# FED3_v6_3.net
KiCad netlist of a schematic drawn in EAGLE
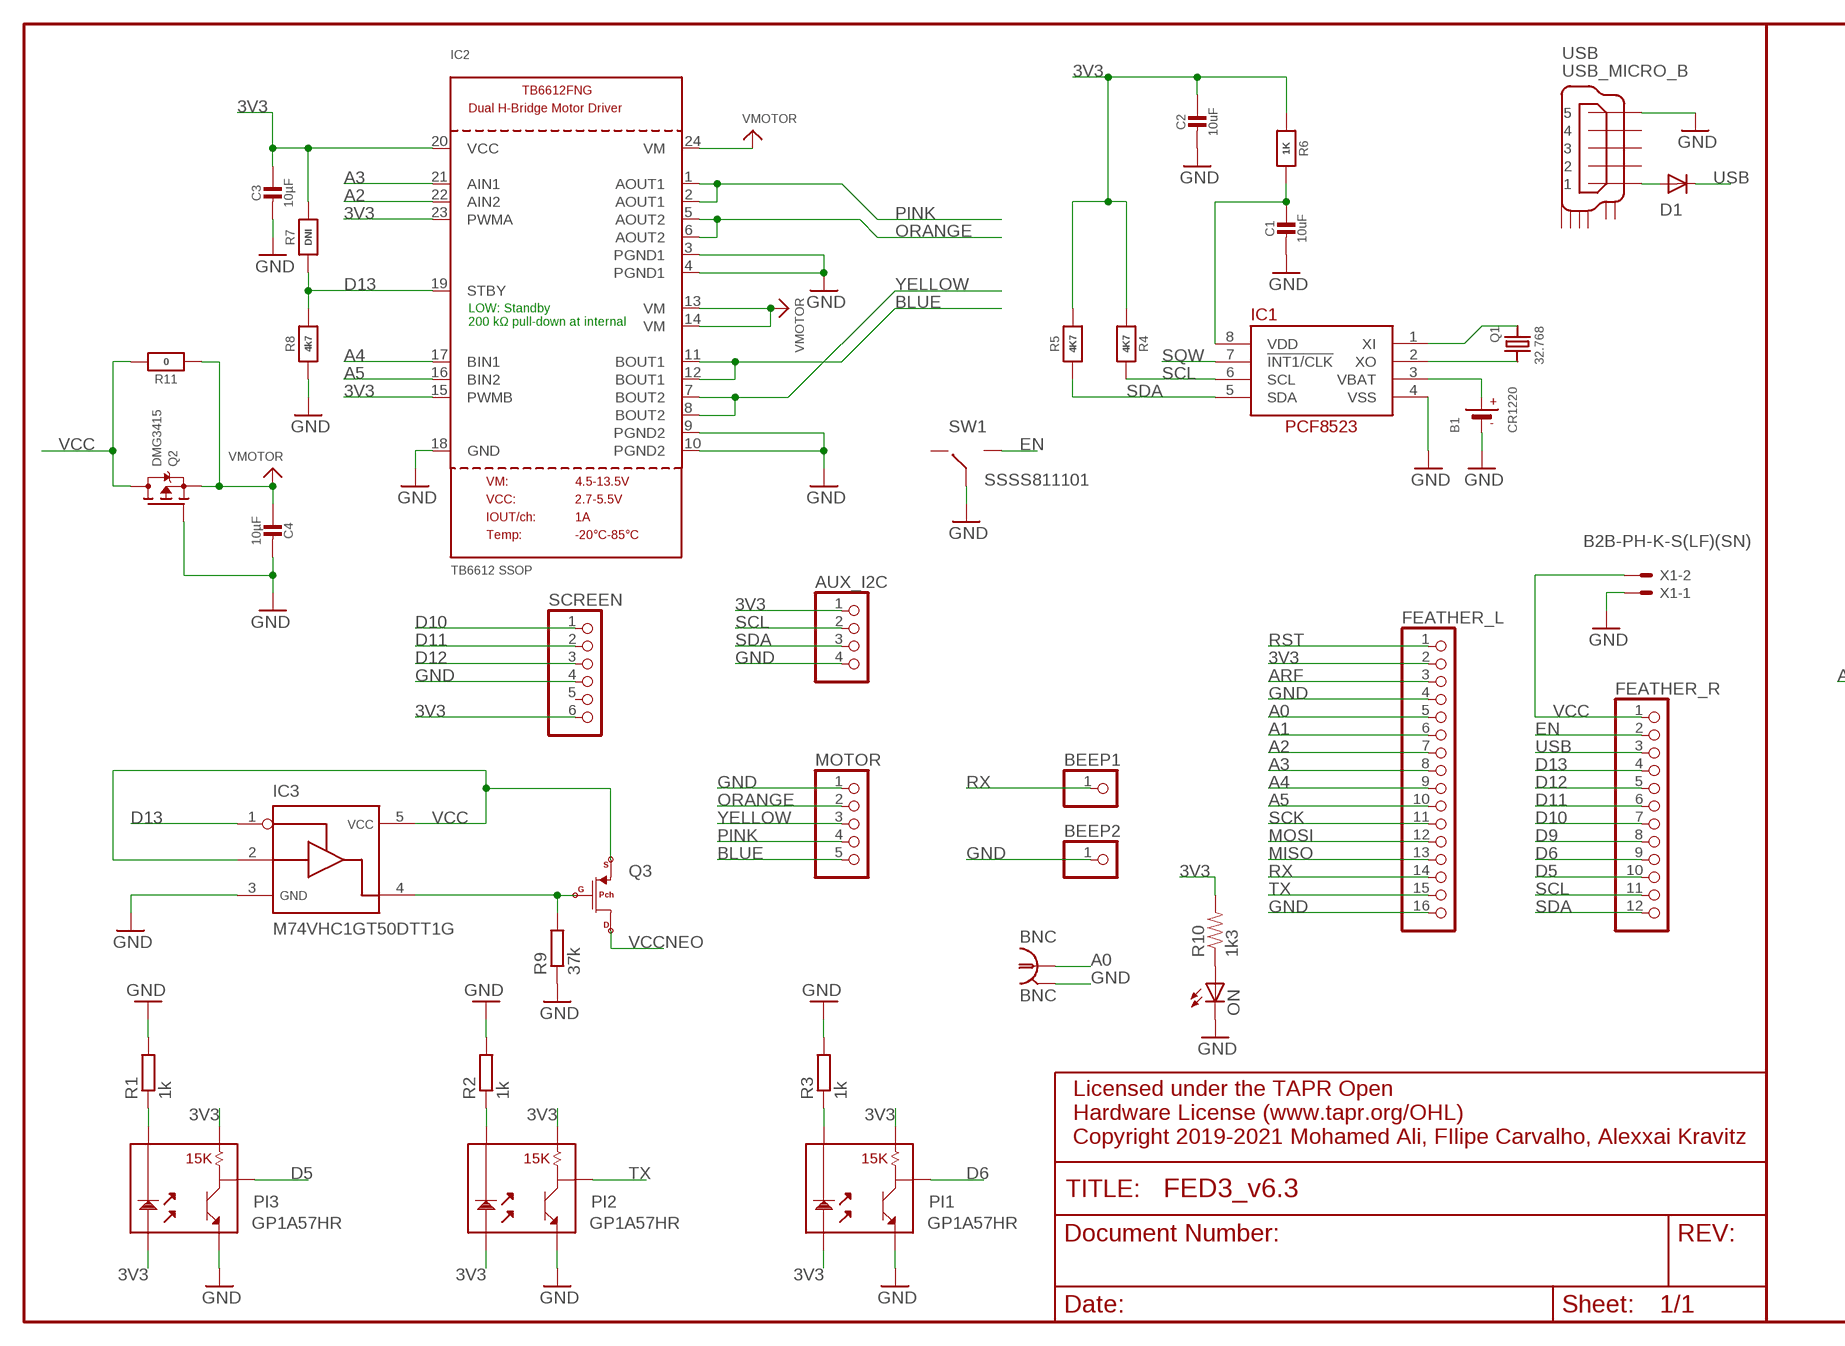
[diagram p0: schematic, sheet 1, part 1 of 2]
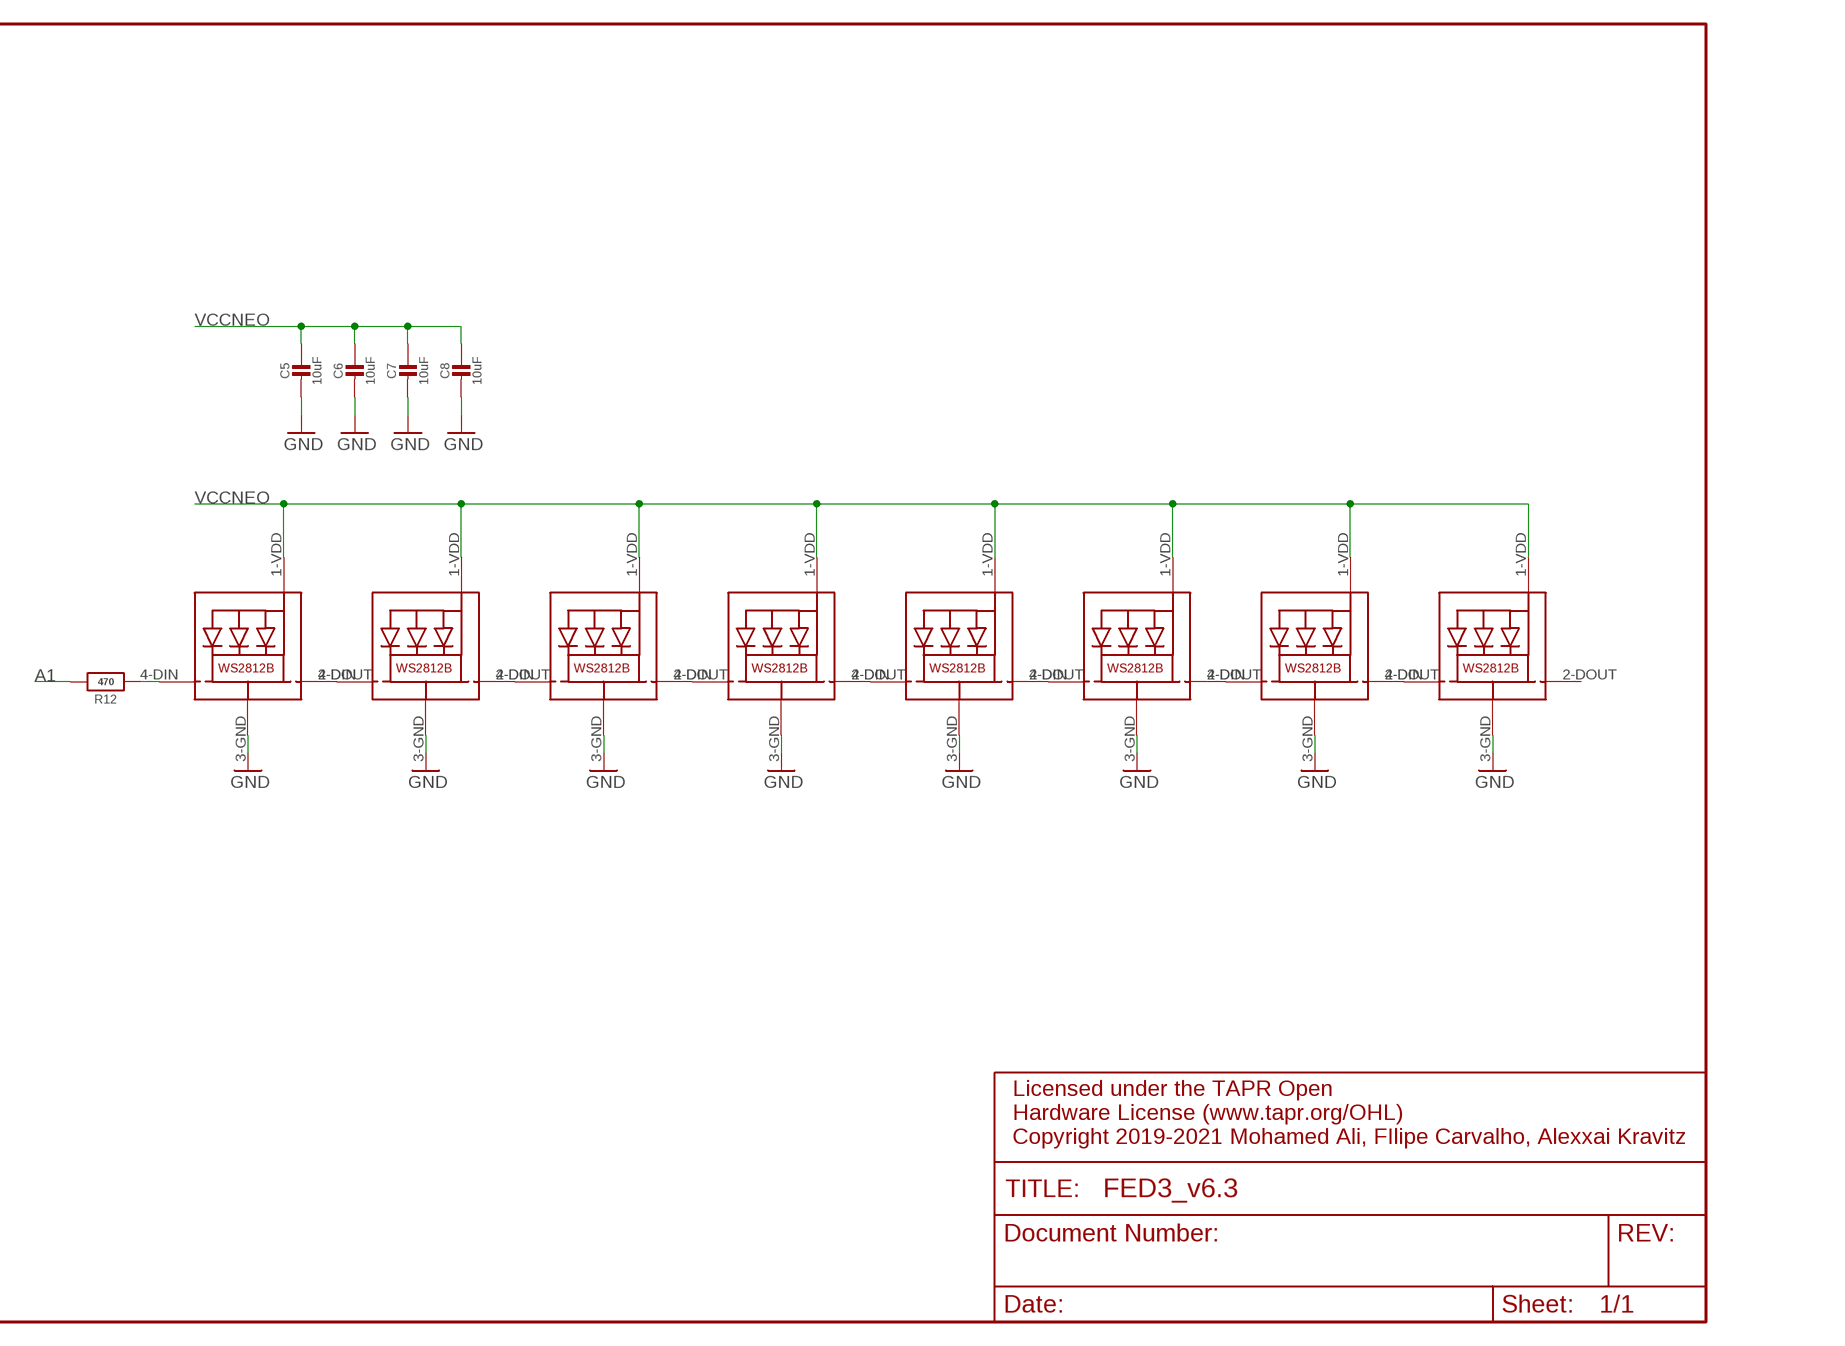
[diagram p1: schematic, sheet 1, part 2 of 2]

(export (version "E")
  (design (tool "Eeschema 10.0.6"))
  (components
    (comp (ref "AUX_I2C")
      (value "PINHD-1X4")
      (footprint "eagle-import:1X04")
      (libsource (lib "eagle-import") (part "PINHD-1X4"))
    )
    (comp (ref "B1")
      (value "CR1220")
      (footprint "eagle-import:CR1220")
      (libsource (lib "eagle-import") (part "BATTERYCR1220_SMT"))
    )
    (comp (ref "BEEP1")
      (value "PINHD-1X1")
      (footprint "eagle-import:1X01")
      (libsource (lib "eagle-import") (part "PINHD-1X1"))
    )
    (comp (ref "BEEP2")
      (value "PINHD-1X1")
      (footprint "eagle-import:1X01")
      (libsource (lib "eagle-import") (part "PINHD-1X1"))
    )
    (comp (ref "BNC")
      (value "BNC")
      (footprint "eagle-import:BNC_RA")
      (libsource (lib "eagle-import") (part "BNC"))
    )
    (comp (ref "C1")
      (value "10uF")
      (footprint "eagle-import:0805-NO")
      (libsource (lib "eagle-import") (part "CAP_CERAMIC0805-NOOUTLINE"))
    )
    (comp (ref "C2")
      (value "10uF")
      (footprint "eagle-import:0805-NO")
      (libsource (lib "eagle-import") (part "CAP_CERAMIC0805-NOOUTLINE"))
    )
    (comp (ref "C3")
      (value "10µF")
      (footprint "eagle-import:0805-NO")
      (libsource (lib "eagle-import") (part "CAP_CERAMIC0805-NOOUTLINE"))
    )
    (comp (ref "C4")
      (value "10µF")
      (footprint "eagle-import:0805-NO")
      (libsource (lib "eagle-import") (part "CAP_CERAMIC0805-NOOUTLINE"))
    )
    (comp (ref "C5")
      (value "10uF")
      (footprint "eagle-import:0805-NO")
      (libsource (lib "eagle-import") (part "CAP_CERAMIC0805-NOOUTLINE"))
    )
    (comp (ref "C6")
      (value "10uF")
      (footprint "eagle-import:0805-NO")
      (libsource (lib "eagle-import") (part "CAP_CERAMIC0805-NOOUTLINE"))
    )
    (comp (ref "C7")
      (value "10uF")
      (footprint "eagle-import:0805-NO")
      (libsource (lib "eagle-import") (part "CAP_CERAMIC0805-NOOUTLINE"))
    )
    (comp (ref "C8")
      (value "10uF")
      (footprint "eagle-import:0805-NO")
      (libsource (lib "eagle-import") (part "CAP_CERAMIC0805-NOOUTLINE"))
    )
    (comp (ref "D1")
      (value "DIODE-DO-214AC")
      (footprint "eagle-import:DO-214AC")
      (libsource (lib "eagle-import") (part "DIODE-DO-214AC"))
    )
    (comp (ref "FEATHER_L")
      (value "PINHD-1X16")
      (footprint "eagle-import:1X16")
      (libsource (lib "eagle-import") (part "PINHD-1X16"))
    )
    (comp (ref "FEATHER_R")
      (value "PINHD-1X12")
      (footprint "eagle-import:1X12")
      (libsource (lib "eagle-import") (part "PINHD-1X12"))
    )
    (comp (ref "IC1")
      (value "RTC_PCF8523T")
      (footprint "eagle-import:SOIC8_150MIL")
      (libsource (lib "eagle-import") (part "RTC_PCF8523T"))
    )
    (comp (ref "IC2")
      (value "TB6612 SSOP")
      (footprint "eagle-import:SSOP24")
      (libsource (lib "eagle-import") (part "TB6612FNGSSOP"))
    )
    (comp (ref "IC3")
      (value "M74VHC1GT50DTT1G")
      (footprint "eagle-import:SOT23-5")
      (libsource (lib "eagle-import") (part "SN74LVC1G125"))
    )
    (comp (ref "LED1")
      (value "WS2812B5050")
      (footprint "eagle-import:WS2812B")
      (libsource (lib "eagle-import") (part "WS2812B5050"))
    )
    (comp (ref "LED2")
      (value "WS2812B5050")
      (footprint "eagle-import:WS2812B")
      (libsource (lib "eagle-import") (part "WS2812B5050"))
    )
    (comp (ref "LED3")
      (value "WS2812B5050")
      (footprint "eagle-import:WS2812B")
      (libsource (lib "eagle-import") (part "WS2812B5050"))
    )
    (comp (ref "LED4")
      (value "WS2812B5050")
      (footprint "eagle-import:WS2812B")
      (libsource (lib "eagle-import") (part "WS2812B5050"))
    )
    (comp (ref "LED5")
      (value "WS2812B5050")
      (footprint "eagle-import:WS2812B")
      (libsource (lib "eagle-import") (part "WS2812B5050"))
    )
    (comp (ref "LED6")
      (value "WS2812B5050")
      (footprint "eagle-import:WS2812B")
      (libsource (lib "eagle-import") (part "WS2812B5050"))
    )
    (comp (ref "LED7")
      (value "WS2812B5050")
      (footprint "eagle-import:WS2812B")
      (libsource (lib "eagle-import") (part "WS2812B5050"))
    )
    (comp (ref "LED8")
      (value "WS2812B5050")
      (footprint "eagle-import:WS2812B")
      (libsource (lib "eagle-import") (part "WS2812B5050"))
    )
    (comp (ref "MOTOR")
      (value "PINHD-1X5")
      (footprint "eagle-import:1X05")
      (libsource (lib "eagle-import") (part "PINHD-1X5"))
    )
    (comp (ref "ON")
      (value "LEDCHIPLED_0603")
      (footprint "eagle-import:CHIPLED_0603")
      (libsource (lib "eagle-import") (part "LEDCHIPLED_0603"))
    )
    (comp (ref "PI1")
      (value "GP1A57HR")
      (footprint "eagle-import:GP1A57HR")
      (libsource (lib "eagle-import") (part "GP1A57HR"))
    )
    (comp (ref "PI2")
      (value "GP1A57HR")
      (footprint "eagle-import:GP1A57HR")
      (libsource (lib "eagle-import") (part "GP1A57HR"))
    )
    (comp (ref "PI3")
      (value "GP1A57HR")
      (footprint "eagle-import:GP1A57HR")
      (libsource (lib "eagle-import") (part "GP1A57HR"))
    )
    (comp (ref "Q1")
      (value "32.768")
      (footprint "eagle-import:CRYSTAL_8X3.8")
      (libsource (lib "eagle-import") (part "CRYSTAL8.0X3.8"))
    )
    (comp (ref "Q2")
      (value "DMG3415")
      (footprint "eagle-import:SOT23-WIDE")
      (libsource (lib "eagle-import") (part "MOSFET-PWIDE"))
    )
    (comp (ref "Q3")
      (value "MOSFET_P-CH")
      (footprint "eagle-import:TSMT3")
      (libsource (lib "eagle-import") (part "MOSFET_P-CH"))
    )
    (comp (ref "R1")
      (value "1k")
      (footprint "eagle-import:R0805")
      (libsource (lib "eagle-import") (part "R-EU_R0805"))
    )
    (comp (ref "R2")
      (value "1k")
      (footprint "eagle-import:R0805")
      (libsource (lib "eagle-import") (part "R-EU_R0805"))
    )
    (comp (ref "R3")
      (value "1k")
      (footprint "eagle-import:R0805")
      (libsource (lib "eagle-import") (part "R-EU_R0805"))
    )
    (comp (ref "R4")
      (value "4K7")
      (footprint "eagle-import:0805-NO")
      (libsource (lib "eagle-import") (part "RESISTOR0805_NOOUTLINE"))
    )
    (comp (ref "R5")
      (value "4K7")
      (footprint "eagle-import:0805-NO")
      (libsource (lib "eagle-import") (part "RESISTOR0805_NOOUTLINE"))
    )
    (comp (ref "R6")
      (value "1K")
      (footprint "eagle-import:0805-NO")
      (libsource (lib "eagle-import") (part "RESISTOR0805_NOOUTLINE"))
    )
    (comp (ref "R7")
      (value "DNI")
      (footprint "eagle-import:0805-NO")
      (libsource (lib "eagle-import") (part "RESISTOR0805_NOOUTLINE"))
    )
    (comp (ref "R8")
      (value "4k7")
      (footprint "eagle-import:0805-NO")
      (libsource (lib "eagle-import") (part "RESISTOR0805_NOOUTLINE"))
    )
    (comp (ref "R9")
      (value "37k")
      (footprint "eagle-import:R0805")
      (libsource (lib "eagle-import") (part "R-EU_R0805"))
    )
    (comp (ref "R10")
      (value "1k3")
      (footprint "eagle-import:0805")
      (libsource (lib "eagle-import") (part "RESISTOR"))
    )
    (comp (ref "R11")
      (value "0")
      (footprint "eagle-import:0805-NO")
      (libsource (lib "eagle-import") (part "RESISTOR0805_NOOUTLINE"))
    )
    (comp (ref "R12")
      (value "470")
      (footprint "eagle-import:0805-NO")
      (libsource (lib "eagle-import") (part "RESISTOR0805_NOOUTLINE"))
    )
    (comp (ref "SCREEN")
      (value "PINHD-1X6")
      (footprint "eagle-import:1X06")
      (libsource (lib "eagle-import") (part "PINHD-1X6"))
    )
    (comp (ref "SW1")
      (value "SSSS811101")
      (footprint "eagle-import:SSSS811101")
      (libsource (lib "eagle-import") (part "SSSS811101"))
    )
    (comp (ref "USB")
      (value "USB_MICRO_B")
      (footprint "eagle-import:ZX62D-B-5P8")
      (libsource (lib "eagle-import") (part "USB_MICRO_B"))
    )
    (comp (ref "X1")
      (value "B2B-PH-K-S(LF)(SN)")
      (footprint "eagle-import:JST-XH-02-PACKAGE-ROUND-PAD")
      (libsource (lib "eagle-import") (part "JST-XH-02-PIN-ROUND-PAD"))
    )
  )
  (nets
    (net (code "1") (name "/3V3") (class "Default")
      (node (ref "AUX_I2C") (pin "1") (pinfunction "1_1") (pintype "passive"))
      (node (ref "C2") (pin "1") (pinfunction "1_1") (pintype "passive"))
      (node (ref "C3") (pin "1") (pinfunction "1_1") (pintype "passive"))
      (node (ref "FEATHER_L") (pin "2") (pinfunction "2_2") (pintype "passive"))
      (node (ref "IC2") (pin "15") (pinfunction "PWMB_15") (pintype "input"))
      (node (ref "IC2") (pin "20") (pinfunction "VCC_20") (pintype "power_in"))
      (node (ref "IC2") (pin "23") (pinfunction "PWMA_23") (pintype "input"))
      (node (ref "PI1") (pin "1") (pinfunction "1_1") (pintype "bidirectional"))
      (node (ref "PI1") (pin "3") (pinfunction "3_3") (pintype "bidirectional"))
      (node (ref "PI2") (pin "1") (pinfunction "1_1") (pintype "bidirectional"))
      (node (ref "PI2") (pin "3") (pinfunction "3_3") (pintype "bidirectional"))
      (node (ref "PI3") (pin "1") (pinfunction "1_1") (pintype "bidirectional"))
      (node (ref "PI3") (pin "3") (pinfunction "3_3") (pintype "bidirectional"))
      (node (ref "R10") (pin "2") (pinfunction "2_2") (pintype "passive"))
      (node (ref "R4") (pin "1") (pinfunction "1_1") (pintype "passive"))
      (node (ref "R5") (pin "2") (pinfunction "2_2") (pintype "passive"))
      (node (ref "R6") (pin "1") (pinfunction "1_1") (pintype "passive"))
      (node (ref "R7") (pin "2") (pinfunction "2_2") (pintype "passive"))
      (node (ref "SCREEN") (pin "6") (pinfunction "6_6") (pintype "passive"))
    )
    (net (code "2") (name "/A0") (class "Default")
      (node (ref "BNC") (pin "1") (pinfunction "1_1") (pintype "passive"))
      (node (ref "FEATHER_L") (pin "5") (pinfunction "5_5") (pintype "passive"))
    )
    (net (code "3") (name "/A1") (class "Default")
      (node (ref "FEATHER_L") (pin "6") (pinfunction "6_6") (pintype "passive"))
      (node (ref "R12") (pin "2") (pinfunction "2_2") (pintype "passive"))
    )
    (net (code "4") (name "/A2") (class "Default")
      (node (ref "FEATHER_L") (pin "7") (pinfunction "7_7") (pintype "passive"))
      (node (ref "IC2") (pin "22") (pinfunction "AIN2_22") (pintype "input"))
    )
    (net (code "5") (name "/A3") (class "Default")
      (node (ref "FEATHER_L") (pin "8") (pinfunction "8_8") (pintype "passive"))
      (node (ref "IC2") (pin "21") (pinfunction "AIN1_21") (pintype "input"))
    )
    (net (code "6") (name "/A4") (class "Default")
      (node (ref "FEATHER_L") (pin "9") (pinfunction "9_9") (pintype "passive"))
      (node (ref "IC2") (pin "17") (pinfunction "BIN1_17") (pintype "input"))
    )
    (net (code "7") (name "/A5") (class "Default")
      (node (ref "FEATHER_L") (pin "10") (pinfunction "10_10") (pintype "passive"))
      (node (ref "IC2") (pin "16") (pinfunction "BIN2_16") (pintype "input"))
    )
    (net (code "8") (name "/ARF") (class "Default")
      (node (ref "FEATHER_L") (pin "3") (pinfunction "3_3") (pintype "passive"))
    )
    (net (code "9") (name "/BLUE") (class "Default")
      (node (ref "IC2") (pin "11") (pinfunction "BOUT1_11") (pintype "output"))
      (node (ref "IC2") (pin "12") (pinfunction "BOUT1_12") (pintype "output"))
      (node (ref "MOTOR") (pin "5") (pinfunction "5_5") (pintype "passive"))
    )
    (net (code "10") (name "/D5") (class "Default")
      (node (ref "FEATHER_R") (pin "10") (pinfunction "10_10") (pintype "passive"))
      (node (ref "PI3") (pin "4") (pinfunction "4_4") (pintype "bidirectional"))
    )
    (net (code "11") (name "/D6") (class "Default")
      (node (ref "FEATHER_R") (pin "9") (pinfunction "9_9") (pintype "passive"))
      (node (ref "PI1") (pin "4") (pinfunction "4_4") (pintype "bidirectional"))
    )
    (net (code "12") (name "/D9") (class "Default")
      (node (ref "FEATHER_R") (pin "8") (pinfunction "8_8") (pintype "passive"))
    )
    (net (code "13") (name "/D10") (class "Default")
      (node (ref "FEATHER_R") (pin "7") (pinfunction "7_7") (pintype "passive"))
      (node (ref "SCREEN") (pin "1") (pinfunction "1_1") (pintype "passive"))
    )
    (net (code "14") (name "/D11") (class "Default")
      (node (ref "FEATHER_R") (pin "6") (pinfunction "6_6") (pintype "passive"))
      (node (ref "SCREEN") (pin "2") (pinfunction "2_2") (pintype "passive"))
    )
    (net (code "15") (name "/D12") (class "Default")
      (node (ref "FEATHER_R") (pin "5") (pinfunction "5_5") (pintype "passive"))
      (node (ref "SCREEN") (pin "3") (pinfunction "3_3") (pintype "passive"))
    )
    (net (code "16") (name "/D13") (class "Default")
      (node (ref "FEATHER_R") (pin "4") (pinfunction "4_4") (pintype "passive"))
      (node (ref "IC2") (pin "19") (pinfunction "STBY_19") (pintype "input"))
      (node (ref "IC3") (pin "1") (pinfunction "P$1_1") (pintype "bidirectional"))
      (node (ref "R7") (pin "1") (pinfunction "1_1") (pintype "passive"))
      (node (ref "R8") (pin "2") (pinfunction "2_2") (pintype "passive"))
    )
    (net (code "17") (name "/EN") (class "Default")
      (node (ref "FEATHER_R") (pin "2") (pinfunction "2_2") (pintype "passive"))
      (node (ref "SW1") (pin "3") (pinfunction "3_3") (pintype "bidirectional"))
    )
    (net (code "18") (name "/MISO") (class "Default")
      (node (ref "FEATHER_L") (pin "13") (pinfunction "13_13") (pintype "passive"))
    )
    (net (code "19") (name "/MOSI") (class "Default")
      (node (ref "FEATHER_L") (pin "12") (pinfunction "12_12") (pintype "passive"))
    )
    (net (code "20") (name "/ORANGE") (class "Default")
      (node (ref "IC2") (pin "5") (pinfunction "AOUT2_5") (pintype "output"))
      (node (ref "IC2") (pin "6") (pinfunction "AOUT2_6") (pintype "output"))
      (node (ref "MOTOR") (pin "2") (pinfunction "2_2") (pintype "passive"))
    )
    (net (code "21") (name "/PINK") (class "Default")
      (node (ref "IC2") (pin "1") (pinfunction "AOUT1_1") (pintype "output"))
      (node (ref "IC2") (pin "2") (pinfunction "AOUT1_2") (pintype "output"))
      (node (ref "MOTOR") (pin "4") (pinfunction "4_4") (pintype "passive"))
    )
    (net (code "22") (name "/RST") (class "Default")
      (node (ref "FEATHER_L") (pin "1") (pinfunction "1_1") (pintype "passive"))
    )
    (net (code "23") (name "/RX") (class "Default")
      (node (ref "BEEP1") (pin "1") (pinfunction "1_1") (pintype "passive"))
      (node (ref "FEATHER_L") (pin "14") (pinfunction "14_14") (pintype "passive"))
    )
    (net (code "24") (name "/SCK") (class "Default")
      (node (ref "FEATHER_L") (pin "11") (pinfunction "11_11") (pintype "passive"))
    )
    (net (code "25") (name "/SCL") (class "Default")
      (node (ref "AUX_I2C") (pin "2") (pinfunction "2_2") (pintype "passive"))
      (node (ref "FEATHER_R") (pin "11") (pinfunction "11_11") (pintype "passive"))
      (node (ref "IC1") (pin "6") (pinfunction "SCL_6") (pintype "bidirectional"))
      (node (ref "R4") (pin "2") (pinfunction "2_2") (pintype "passive"))
    )
    (net (code "26") (name "/SDA") (class "Default")
      (node (ref "AUX_I2C") (pin "3") (pinfunction "3_3") (pintype "passive"))
      (node (ref "FEATHER_R") (pin "12") (pinfunction "12_12") (pintype "passive"))
      (node (ref "IC1") (pin "5") (pinfunction "SDA_5") (pintype "bidirectional"))
      (node (ref "R5") (pin "1") (pinfunction "1_1") (pintype "passive"))
    )
    (net (code "27") (name "/SQW") (class "Default")
      (node (ref "IC1") (pin "7") (pinfunction "~{INT1/CLK}_7") (pintype "output"))
    )
    (net (code "28") (name "/TX") (class "Default")
      (node (ref "FEATHER_L") (pin "15") (pinfunction "15_15") (pintype "passive"))
      (node (ref "PI2") (pin "4") (pinfunction "4_4") (pintype "bidirectional"))
    )
    (net (code "29") (name "/USB") (class "Default")
      (node (ref "D1") (pin "C") (pinfunction "C_C") (pintype "passive"))
      (node (ref "FEATHER_R") (pin "3") (pinfunction "3_3") (pintype "passive"))
    )
    (net (code "30") (name "/VCC") (class "Default")
      (node (ref "FEATHER_R") (pin "1") (pinfunction "1_1") (pintype "passive"))
      (node (ref "IC3") (pin "2") (pinfunction "P$2_2") (pintype "bidirectional"))
      (node (ref "IC3") (pin "5") (pinfunction "P$5_5") (pintype "bidirectional"))
      (node (ref "Q2") (pin "3") (pinfunction "D_3") (pintype "passive"))
      (node (ref "Q3") (pin "P$2") (pinfunction "S_P$2") (pintype "passive"))
      (node (ref "R11") (pin "2") (pinfunction "2_2") (pintype "passive"))
      (node (ref "X1") (pin "2") (pinfunction "S_2") (pintype "passive"))
    )
    (net (code "31") (name "/VCCNEO") (class "Default")
      (node (ref "C5") (pin "1") (pinfunction "1_1") (pintype "passive"))
      (node (ref "C6") (pin "1") (pinfunction "1_1") (pintype "passive"))
      (node (ref "C7") (pin "1") (pinfunction "1_1") (pintype "passive"))
      (node (ref "C8") (pin "1") (pinfunction "1_1") (pintype "passive"))
      (node (ref "LED1") (pin "1-VDD") (pinfunction "VDD_1-VDD") (pintype "power_in"))
      (node (ref "LED2") (pin "1-VDD") (pinfunction "VDD_1-VDD") (pintype "power_in"))
      (node (ref "LED3") (pin "1-VDD") (pinfunction "VDD_1-VDD") (pintype "power_in"))
      (node (ref "LED4") (pin "1-VDD") (pinfunction "VDD_1-VDD") (pintype "power_in"))
      (node (ref "LED5") (pin "1-VDD") (pinfunction "VDD_1-VDD") (pintype "power_in"))
      (node (ref "LED6") (pin "1-VDD") (pinfunction "VDD_1-VDD") (pintype "power_in"))
      (node (ref "LED7") (pin "1-VDD") (pinfunction "VDD_1-VDD") (pintype "power_in"))
      (node (ref "LED8") (pin "1-VDD") (pinfunction "VDD_1-VDD") (pintype "power_in"))
      (node (ref "Q3") (pin "P$3") (pinfunction "D_P$3") (pintype "passive"))
    )
    (net (code "32") (name "/YELLOW") (class "Default")
      (node (ref "IC2") (pin "7") (pinfunction "BOUT2_7") (pintype "output"))
      (node (ref "IC2") (pin "8") (pinfunction "BOUT2_8") (pintype "output"))
      (node (ref "MOTOR") (pin "3") (pinfunction "3_3") (pintype "passive"))
    )
    (net (code "33") (name "GND") (class "Default")
      (node (ref "AUX_I2C") (pin "4") (pinfunction "4_4") (pintype "passive"))
      (node (ref "B1") (pin "-") (pinfunction "-_-") (pintype "passive"))
      (node (ref "BEEP2") (pin "1") (pinfunction "1_1") (pintype "passive"))
      (node (ref "BNC") (pin "2") (pinfunction "2_2") (pintype "passive"))
      (node (ref "C1") (pin "2") (pinfunction "2_2") (pintype "passive"))
      (node (ref "C2") (pin "2") (pinfunction "2_2") (pintype "passive"))
      (node (ref "C3") (pin "2") (pinfunction "2_2") (pintype "passive"))
      (node (ref "C4") (pin "2") (pinfunction "2_2") (pintype "passive"))
      (node (ref "C5") (pin "2") (pinfunction "2_2") (pintype "passive"))
      (node (ref "C6") (pin "2") (pinfunction "2_2") (pintype "passive"))
      (node (ref "C7") (pin "2") (pinfunction "2_2") (pintype "passive"))
      (node (ref "C8") (pin "2") (pinfunction "2_2") (pintype "passive"))
      (node (ref "FEATHER_L") (pin "16") (pinfunction "16_16") (pintype "passive"))
      (node (ref "FEATHER_L") (pin "4") (pinfunction "4_4") (pintype "passive"))
      (node (ref "IC1") (pin "4") (pinfunction "VSS_4") (pintype "power_in"))
      (node (ref "IC2") (pin "10") (pinfunction "PGND2_10") (pintype "power_in"))
      (node (ref "IC2") (pin "18") (pinfunction "GND_18") (pintype "power_in"))
      (node (ref "IC2") (pin "3") (pinfunction "PGND1_3") (pintype "power_in"))
      (node (ref "IC2") (pin "4") (pinfunction "PGND1_4") (pintype "power_in"))
      (node (ref "IC2") (pin "9") (pinfunction "PGND2_9") (pintype "power_in"))
      (node (ref "IC3") (pin "3") (pinfunction "P$3_3") (pintype "bidirectional"))
      (node (ref "LED1") (pin "3-GND") (pinfunction "GND_3-GND") (pintype "power_in"))
      (node (ref "LED2") (pin "3-GND") (pinfunction "GND_3-GND") (pintype "power_in"))
      (node (ref "LED3") (pin "3-GND") (pinfunction "GND_3-GND") (pintype "power_in"))
      (node (ref "LED4") (pin "3-GND") (pinfunction "GND_3-GND") (pintype "power_in"))
      (node (ref "LED5") (pin "3-GND") (pinfunction "GND_3-GND") (pintype "power_in"))
      (node (ref "LED6") (pin "3-GND") (pinfunction "GND_3-GND") (pintype "power_in"))
      (node (ref "LED7") (pin "3-GND") (pinfunction "GND_3-GND") (pintype "power_in"))
      (node (ref "LED8") (pin "3-GND") (pinfunction "GND_3-GND") (pintype "power_in"))
      (node (ref "MOTOR") (pin "1") (pinfunction "1_1") (pintype "passive"))
      (node (ref "ON") (pin "C") (pinfunction "C_C") (pintype "passive"))
      (node (ref "PI1") (pin "5") (pinfunction "5_5") (pintype "bidirectional"))
      (node (ref "PI2") (pin "5") (pinfunction "5_5") (pintype "bidirectional"))
      (node (ref "PI3") (pin "5") (pinfunction "5_5") (pintype "bidirectional"))
      (node (ref "Q2") (pin "1") (pinfunction "G_1") (pintype "passive"))
      (node (ref "R1") (pin "2") (pinfunction "2_2") (pintype "passive"))
      (node (ref "R2") (pin "2") (pinfunction "2_2") (pintype "passive"))
      (node (ref "R3") (pin "2") (pinfunction "2_2") (pintype "passive"))
      (node (ref "R8") (pin "1") (pinfunction "1_1") (pintype "passive"))
      (node (ref "R9") (pin "1") (pinfunction "1_1") (pintype "passive"))
      (node (ref "SCREEN") (pin "4") (pinfunction "4_4") (pintype "passive"))
      (node (ref "SW1") (pin "2") (pinfunction "2_2") (pintype "bidirectional"))
      (node (ref "USB") (pin "P$5") (pinfunction "5_P$5") (pintype "bidirectional"))
      (node (ref "X1") (pin "1") (pinfunction "S_1") (pintype "passive"))
    )
    (net (code "34") (name "Net-(B1-+)") (class "Default")
      (node (ref "B1") (pin "+$1") (pinfunction "+_+$1") (pintype "passive"))
      (node (ref "IC1") (pin "3") (pinfunction "VBAT_3") (pintype "power_in"))
    )
    (net (code "35") (name "Net-(IC1-VDD)") (class "Default")
      (node (ref "C1") (pin "1") (pinfunction "1_1") (pintype "passive"))
      (node (ref "IC1") (pin "8") (pinfunction "VDD_8") (pintype "power_in"))
      (node (ref "R6") (pin "2") (pinfunction "2_2") (pintype "passive"))
    )
    (net (code "36") (name "Net-(IC1-XI)") (class "Default")
      (node (ref "IC1") (pin "1") (pinfunction "XI_1") (pintype "input"))
      (node (ref "Q1") (pin "P$1") (pinfunction "1_P$1") (pintype "passive"))
    )
    (net (code "37") (name "Net-(IC1-XO)") (class "Default")
      (node (ref "IC1") (pin "2") (pinfunction "XO_2") (pintype "output"))
      (node (ref "Q1") (pin "P$4") (pinfunction "2_P$4") (pintype "passive"))
    )
    (net (code "38") (name "Net-(IC3-P$4)") (class "Default")
      (node (ref "IC3") (pin "4") (pinfunction "P$4_4") (pintype "bidirectional"))
      (node (ref "Q3") (pin "P$1") (pinfunction "G_P$1") (pintype "passive"))
      (node (ref "R9") (pin "2") (pinfunction "2_2") (pintype "passive"))
    )
    (net (code "39") (name "Net-(LED1-DI)") (class "Default")
      (node (ref "LED1") (pin "4-DIN") (pinfunction "DI_4-DIN") (pintype "input"))
      (node (ref "R12") (pin "1") (pinfunction "1_1") (pintype "passive"))
    )
    (net (code "40") (name "Net-(LED1-DO)") (class "Default")
      (node (ref "LED1") (pin "2-DOUT") (pinfunction "DO_2-DOUT") (pintype "output"))
      (node (ref "LED2") (pin "4-DIN") (pinfunction "DI_4-DIN") (pintype "input"))
    )
    (net (code "41") (name "Net-(LED2-DO)") (class "Default")
      (node (ref "LED2") (pin "2-DOUT") (pinfunction "DO_2-DOUT") (pintype "output"))
      (node (ref "LED3") (pin "4-DIN") (pinfunction "DI_4-DIN") (pintype "input"))
    )
    (net (code "42") (name "Net-(LED3-DO)") (class "Default")
      (node (ref "LED3") (pin "2-DOUT") (pinfunction "DO_2-DOUT") (pintype "output"))
      (node (ref "LED4") (pin "4-DIN") (pinfunction "DI_4-DIN") (pintype "input"))
    )
    (net (code "43") (name "Net-(LED4-DO)") (class "Default")
      (node (ref "LED4") (pin "2-DOUT") (pinfunction "DO_2-DOUT") (pintype "output"))
      (node (ref "LED5") (pin "4-DIN") (pinfunction "DI_4-DIN") (pintype "input"))
    )
    (net (code "44") (name "Net-(LED5-DO)") (class "Default")
      (node (ref "LED5") (pin "2-DOUT") (pinfunction "DO_2-DOUT") (pintype "output"))
      (node (ref "LED6") (pin "4-DIN") (pinfunction "DI_4-DIN") (pintype "input"))
    )
    (net (code "45") (name "Net-(LED6-DO)") (class "Default")
      (node (ref "LED6") (pin "2-DOUT") (pinfunction "DO_2-DOUT") (pintype "output"))
      (node (ref "LED7") (pin "4-DIN") (pinfunction "DI_4-DIN") (pintype "input"))
    )
    (net (code "46") (name "Net-(LED7-DO)") (class "Default")
      (node (ref "LED7") (pin "2-DOUT") (pinfunction "DO_2-DOUT") (pintype "output"))
      (node (ref "LED8") (pin "4-DIN") (pinfunction "DI_4-DIN") (pintype "input"))
    )
    (net (code "47") (name "Net-(ON-PadA)") (class "Default")
      (node (ref "ON") (pin "A") (pinfunction "A_A") (pintype "passive"))
      (node (ref "R10") (pin "1") (pinfunction "1_1") (pintype "passive"))
    )
    (net (code "48") (name "Net-(PI1-Pad2)") (class "Default")
      (node (ref "PI1") (pin "2") (pinfunction "2_2") (pintype "bidirectional"))
      (node (ref "R3") (pin "1") (pinfunction "1_1") (pintype "passive"))
    )
    (net (code "49") (name "Net-(PI2-Pad2)") (class "Default")
      (node (ref "PI2") (pin "2") (pinfunction "2_2") (pintype "bidirectional"))
      (node (ref "R2") (pin "1") (pinfunction "1_1") (pintype "passive"))
    )
    (net (code "50") (name "Net-(PI3-Pad2)") (class "Default")
      (node (ref "PI3") (pin "2") (pinfunction "2_2") (pintype "bidirectional"))
      (node (ref "R1") (pin "1") (pinfunction "1_1") (pintype "passive"))
    )
    (net (code "51") (name "Net-(USB-1)") (class "Default")
      (node (ref "D1") (pin "A") (pinfunction "A_A") (pintype "passive"))
      (node (ref "USB") (pin "P$1") (pinfunction "1_P$1") (pintype "bidirectional"))
    )
    (net (code "52") (name "VMOTOR") (class "Default")
      (node (ref "C4") (pin "1") (pinfunction "1_1") (pintype "passive"))
      (node (ref "IC2") (pin "13") (pinfunction "VM_13") (pintype "power_in"))
      (node (ref "IC2") (pin "14") (pinfunction "VM_14") (pintype "power_in"))
      (node (ref "IC2") (pin "24") (pinfunction "VM_24") (pintype "power_in"))
      (node (ref "Q2") (pin "2") (pinfunction "S_2") (pintype "passive"))
      (node (ref "R11") (pin "1") (pinfunction "1_1") (pintype "passive"))
    )
    (net (code "53") (name "unconnected-(LED8-DO-Pad2-DOUT)") (class "Default")
      (node (ref "LED8") (pin "2-DOUT") (pinfunction "DO_2-DOUT") (pintype "output"))
    )
    (net (code "54") (name "unconnected-(SCREEN-Pad5)") (class "Default")
      (node (ref "SCREEN") (pin "5") (pinfunction "5_5") (pintype "passive"))
    )
    (net (code "55") (name "unconnected-(SW1-Pad1)") (class "Default")
      (node (ref "SW1") (pin "1") (pinfunction "1_1") (pintype "bidirectional"))
    )
    (net (code "56") (name "unconnected-(USB-2-PadP$2)") (class "Default")
      (node (ref "USB") (pin "P$2") (pinfunction "2_P$2") (pintype "bidirectional"))
    )
    (net (code "57") (name "unconnected-(USB-3-PadP$3)") (class "Default")
      (node (ref "USB") (pin "P$3") (pinfunction "3_P$3") (pintype "bidirectional"))
    )
    (net (code "58") (name "unconnected-(USB-4-PadP$4)") (class "Default")
      (node (ref "USB") (pin "P$4") (pinfunction "4_P$4") (pintype "bidirectional"))
    )
    (net (code "59") (name "unconnected-(USB-P$1-PadSHIELD_3)") (class "Default")
      (node (ref "USB") (pin "SHIELD_3") (pinfunction "P$1_SHIELD_3") (pintype "bidirectional"))
    )
    (net (code "60") (name "unconnected-(USB-P$2-PadSHIELD_1)") (class "Default")
      (node (ref "USB") (pin "SHIELD_1") (pinfunction "P$2_SHIELD_1") (pintype "bidirectional"))
    )
    (net (code "61") (name "unconnected-(USB-P$3-PadSHIELD_2)") (class "Default")
      (node (ref "USB") (pin "SHIELD_2") (pinfunction "P$3_SHIELD_2") (pintype "bidirectional"))
    )
    (net (code "62") (name "unconnected-(USB-P$4-PadSHIELD_4)") (class "Default")
      (node (ref "USB") (pin "SHIELD_4") (pinfunction "P$4_SHIELD_4") (pintype "bidirectional"))
    )
    (net (code "63") (name "unconnected-(USB-P$5-PadP$6)") (class "Default")
      (node (ref "USB") (pin "P$6") (pinfunction "P$5_P$6") (pintype "bidirectional"))
    )
    (net (code "64") (name "unconnected-(USB-P$6-PadP$7)") (class "Default")
      (node (ref "USB") (pin "P$7") (pinfunction "P$6_P$7") (pintype "bidirectional"))
    )
  )
)
